# LPCB279_-_RM57_LAUNCH.net
KiCad netlist of a schematic drawn in Altium Designer
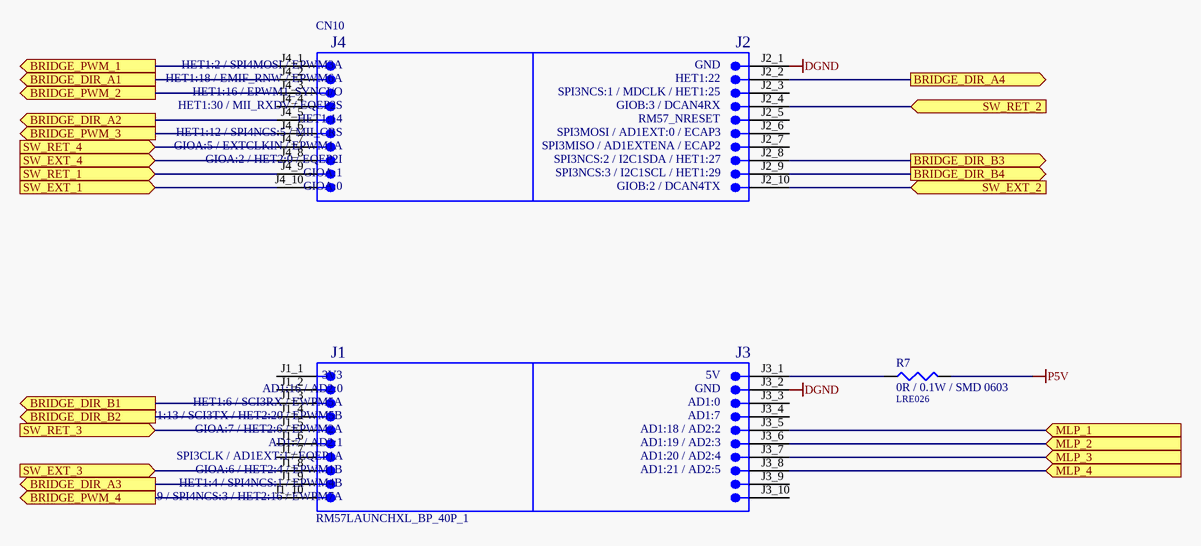
[diagram p0: LPCB279 - RM57 LAUNCH.SchDoc]

(export (version "E")
  (design (tool "Eeschema 10.0.6"))
  (components
    (comp (ref "CN10")
      (value "RM57LAUNCHXL_BP_40P_1")
      (footprint "RM57LAUNCHXL_BP_40P_1")
      (description "Connector, RM57L843 LaunchXL, 40Pin Boosterpack Site1")
      (libsource (lib "LDL_Connectors") (part "RM57LAUNCHXL_BP_40P_1"))
    )
    (comp (ref "R7")
      (value "0R / 0.1W / SMD 0603")
      (footprint "LFP020__CR1608-0603-IPC7351_B")
      (description "Resistor, Ceramic Chip, 0R, 0.1W, SMD 0603 [LRE026]")
      (fields (field (name "LDL_NUMBER") "LRE026"))
      (libsource (lib "LDL_Resistors") (part "0R / 0.1W / SMD 0603"))
    )
  )
  (nets
    (net (code "1") (name "/BRIDGE_DIR_A1") (class "Default")
      (node (ref "CN10") (pin "J4_2") (pintype "passive"))
    )
    (net (code "2") (name "/BRIDGE_DIR_A2") (class "Default")
      (node (ref "CN10") (pin "J4_5") (pintype "passive"))
    )
    (net (code "3") (name "/BRIDGE_DIR_A3") (class "Default")
      (node (ref "CN10") (pin "J1_9") (pintype "passive"))
    )
    (net (code "4") (name "/BRIDGE_DIR_A4") (class "Default")
      (node (ref "CN10") (pin "J2_2") (pintype "passive"))
    )
    (net (code "5") (name "/BRIDGE_DIR_B1") (class "Default")
      (node (ref "CN10") (pin "J1_3") (pintype "passive"))
    )
    (net (code "6") (name "/BRIDGE_DIR_B2") (class "Default")
      (node (ref "CN10") (pin "J1_4") (pintype "passive"))
    )
    (net (code "7") (name "/BRIDGE_DIR_B3") (class "Default")
      (node (ref "CN10") (pin "J2_8") (pintype "passive"))
    )
    (net (code "8") (name "/BRIDGE_DIR_B4") (class "Default")
      (node (ref "CN10") (pin "J2_9") (pintype "passive"))
    )
    (net (code "9") (name "/BRIDGE_PWM_1") (class "Default")
      (node (ref "CN10") (pin "J4_1") (pintype "passive"))
    )
    (net (code "10") (name "/BRIDGE_PWM_2") (class "Default")
      (node (ref "CN10") (pin "J4_3") (pintype "passive"))
    )
    (net (code "11") (name "/BRIDGE_PWM_3") (class "Default")
      (node (ref "CN10") (pin "J4_6") (pintype "passive"))
    )
    (net (code "12") (name "/BRIDGE_PWM_4") (class "Default")
      (node (ref "CN10") (pin "J1_10") (pintype "passive"))
    )
    (net (code "13") (name "/MLP_1") (class "Default") (node (ref "CN10") (pin "J3_5") (pintype "passive")))
    (net (code "14") (name "/MLP_2") (class "Default") (node (ref "CN10") (pin "J3_6") (pintype "passive")))
    (net (code "15") (name "/MLP_3") (class "Default") (node (ref "CN10") (pin "J3_7") (pintype "passive")))
    (net (code "16") (name "/MLP_4") (class "Default") (node (ref "CN10") (pin "J3_8") (pintype "passive")))
    (net (code "17") (name "/SW_EXT_1") (class "Default")
      (node (ref "CN10") (pin "J4_10") (pintype "passive"))
    )
    (net (code "18") (name "/SW_EXT_2") (class "Default")
      (node (ref "CN10") (pin "J2_10") (pintype "passive"))
    )
    (net (code "19") (name "/SW_EXT_3") (class "Default")
      (node (ref "CN10") (pin "J1_8") (pintype "passive"))
    )
    (net (code "20") (name "/SW_EXT_4") (class "Default")
      (node (ref "CN10") (pin "J4_8") (pintype "passive"))
    )
    (net (code "21") (name "/SW_RET_1") (class "Default")
      (node (ref "CN10") (pin "J4_9") (pintype "passive"))
    )
    (net (code "22") (name "/SW_RET_2") (class "Default")
      (node (ref "CN10") (pin "J2_4") (pintype "passive"))
    )
    (net (code "23") (name "/SW_RET_3") (class "Default")
      (node (ref "CN10") (pin "J1_5") (pintype "passive"))
    )
    (net (code "24") (name "/SW_RET_4") (class "Default")
      (node (ref "CN10") (pin "J4_7") (pintype "passive"))
    )
    (net (code "25") (name "DGND") (class "Default")
      (node (ref "CN10") (pin "J2_1") (pintype "passive"))
      (node (ref "CN10") (pin "J3_2") (pintype "passive"))
    )
    (net (code "26") (name "Net-(CN10-PadJ3_1)") (class "Default")
      (node (ref "CN10") (pin "J3_1") (pintype "passive"))
      (node (ref "R7") (pin "1") (pintype "passive"))
    )
    (net (code "27") (name "P5V") (class "Default") (node (ref "R7") (pin "2") (pintype "passive")))
    (net (code "28") (name "unconnected-(CN10-PadJ1_1)") (class "Default")
      (node (ref "CN10") (pin "J1_1") (pintype "passive"))
    )
    (net (code "29") (name "unconnected-(CN10-PadJ1_2)") (class "Default")
      (node (ref "CN10") (pin "J1_2") (pintype "passive"))
    )
    (net (code "30") (name "unconnected-(CN10-PadJ1_6)") (class "Default")
      (node (ref "CN10") (pin "J1_6") (pintype "passive"))
    )
    (net (code "31") (name "unconnected-(CN10-PadJ1_7)") (class "Default")
      (node (ref "CN10") (pin "J1_7") (pintype "passive"))
    )
    (net (code "32") (name "unconnected-(CN10-PadJ2_3)") (class "Default")
      (node (ref "CN10") (pin "J2_3") (pintype "passive"))
    )
    (net (code "33") (name "unconnected-(CN10-PadJ2_5)") (class "Default")
      (node (ref "CN10") (pin "J2_5") (pintype "passive"))
    )
    (net (code "34") (name "unconnected-(CN10-PadJ2_6)") (class "Default")
      (node (ref "CN10") (pin "J2_6") (pintype "passive"))
    )
    (net (code "35") (name "unconnected-(CN10-PadJ2_7)") (class "Default")
      (node (ref "CN10") (pin "J2_7") (pintype "passive"))
    )
    (net (code "36") (name "unconnected-(CN10-PadJ3_3)") (class "Default")
      (node (ref "CN10") (pin "J3_3") (pintype "passive"))
    )
    (net (code "37") (name "unconnected-(CN10-PadJ3_4)") (class "Default")
      (node (ref "CN10") (pin "J3_4") (pintype "passive"))
    )
    (net (code "38") (name "unconnected-(CN10-PadJ3_9)") (class "Default")
      (node (ref "CN10") (pin "J3_9") (pintype "passive"))
    )
    (net (code "39") (name "unconnected-(CN10-PadJ3_10)") (class "Default")
      (node (ref "CN10") (pin "J3_10") (pintype "passive"))
    )
    (net (code "40") (name "unconnected-(CN10-PadJ4_4)") (class "Default")
      (node (ref "CN10") (pin "J4_4") (pintype "passive"))
    )
  )
)
